# Top.net
KiCad netlist of a schematic drawn in Altium Designer
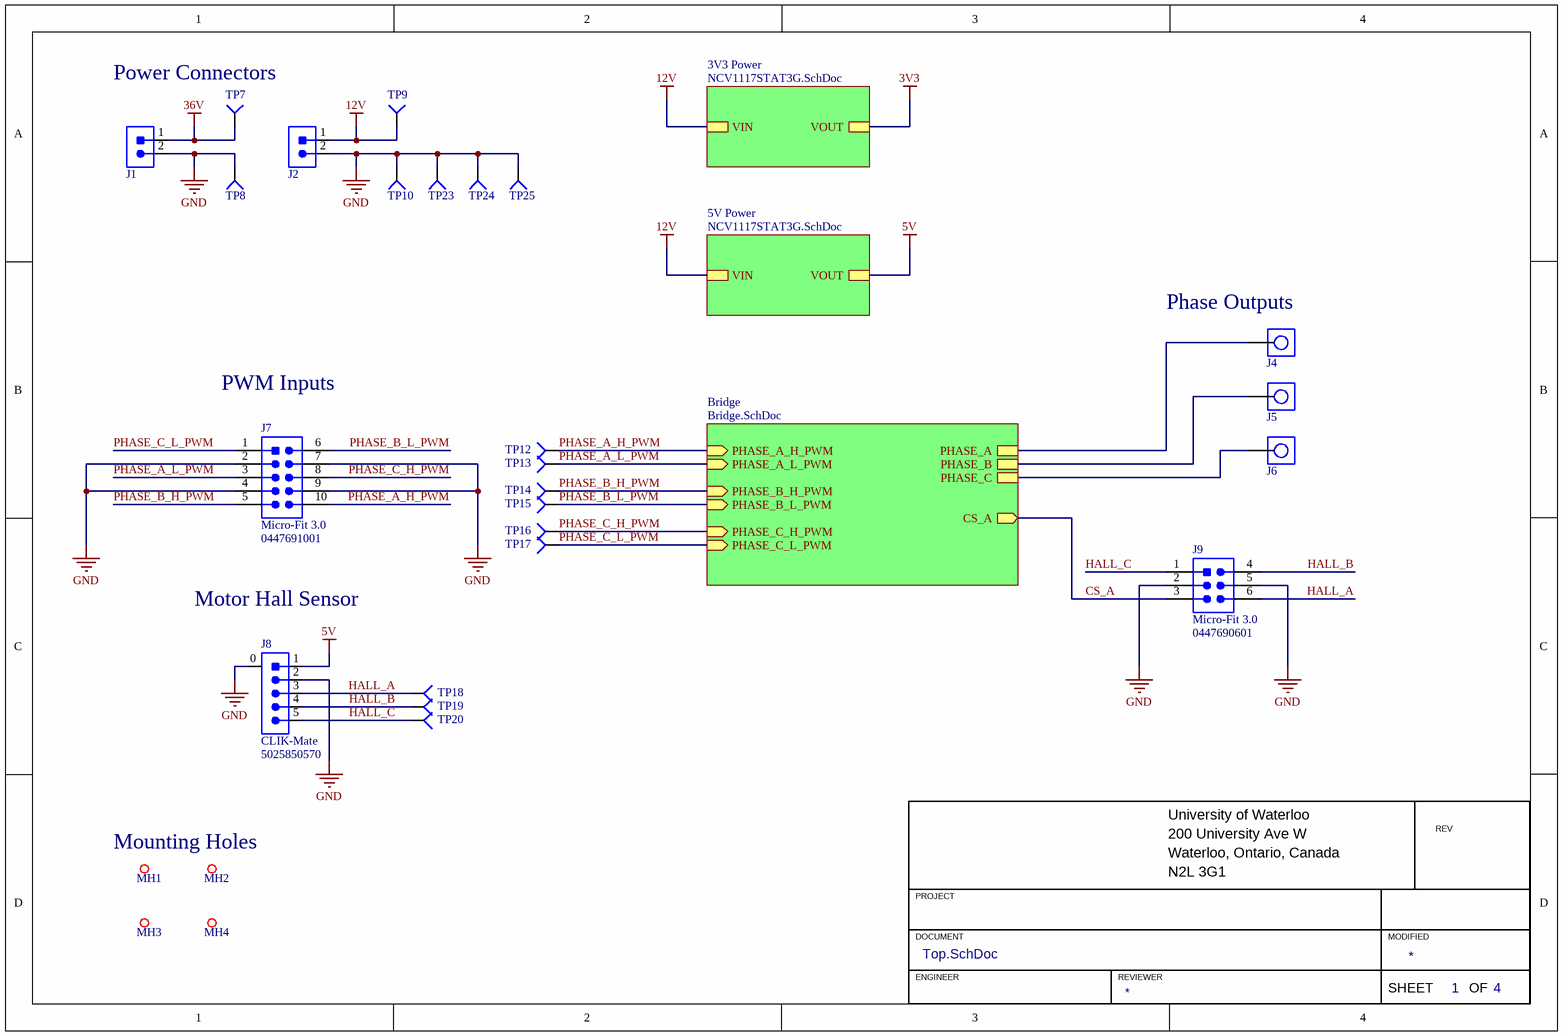
[diagram p0: Top.SchDoc]

(export (version "E")
  (design (tool "Eeschema 10.0.6"))
  (components
    (comp (ref "J1")
      (value "CON_2POS_XT90")
      (footprint "XT90")
      (description "XT60 CONNECTORS MALE/FEMALE PAIR")
      (libsource (lib "Personal_Schematic_Library_2022") (part "CON_2POS_XT90"))
    )
    (comp (ref "J2")
      (value "CON_2POS_XT60")
      (footprint "XT60")
      (description "XT60 CONNECTORS MALE/FEMALE PAIR")
      (libsource (lib "Personal_Schematic_Library_2022") (part "CON_2POS_XT60"))
    )
    (comp (ref "J4")
      (value "CT3151SP-4")
      (footprint "CALTEST_BANANA_JACK_YELLOW")
      (description "CONN BANANA JACK SOLDER YELLOW")
      (libsource (lib "UWRT_Schematic_Library_2020") (part "CON_BANANA_YELLOW_25A"))
    )
    (comp (ref "J5")
      (value "CT3151SP-5")
      (footprint "CALTEST_BANANA_JACK_GREEN")
      (description "CONN BANANA JACK SOLDER GREEN")
      (libsource (lib "UWRT_Schematic_Library_2020") (part "CON_BANANA_GREEN_25A"))
    )
    (comp (ref "J6")
      (value "CT3151SP-6")
      (footprint "CALTEST_BANANA_JACK_BLUE")
      (description "CONN BANANA JACK SOLDER BLUE")
      (libsource (lib "UWRT_Schematic_Library_2020") (part "CON_BANANA_BLUE_25A"))
    )
    (comp (ref "J7")
      (value "0447691001")
      (footprint "MOLEX-0447691001")
      (description "CONN RCPT 10POS 0.118 TIN PCB")
      (fields
        (field (name "FAMILY") "Micro-Fit 3.0")
        (field (name "MANUFACTURER PART NUMBER 1") "0447691001")
      )
      (libsource (lib "UWRT_Schematic_Library_2020") (part "CON_MOLEX-RCPT_5x2_TH"))
    )
    (comp (ref "J8")
      (value "CON_5M_SM_RA")
      (footprint "MOLEX-5025850570")
      (description "CONN HEADER SMD RIGHT ANGLE 1.5MM PITCH")
      (fields (field (name "FAMILY") "CLIK-Mate") (field (name "MANUFACTURER PART NUMBER 1") "5025850570"))
      (libsource (lib "UWRT_Schematic_Library_2020") (part "CON_5M_SM_RA"))
    )
    (comp (ref "J9")
      (value "0447690601")
      (footprint "MOLEX-0447690601")
      (description "CONN RCPT 6POS 0.118 TIN PCB")
      (fields
        (field (name "FAMILY") "Micro-Fit 3.0")
        (field (name "MANUFACTURER PART NUMBER 1") "0447690601")
      )
      (libsource (lib "UWRT_Schematic_Library_2020") (part "CON_MOLEX-RCPT_3x2_TH"))
    )
    (comp (ref "MH1")
      (value "MOUNTING_HOLE_M3")
      (footprint "MOUNTING_HOLE_3mm")
      (libsource (lib "UWRT_Schematic_Library_2020") (part "MOUNTING_HOLE_M3"))
    )
    (comp (ref "MH2")
      (value "MOUNTING_HOLE_M3")
      (footprint "MOUNTING_HOLE_3mm")
      (libsource (lib "UWRT_Schematic_Library_2020") (part "MOUNTING_HOLE_M3"))
    )
    (comp (ref "MH3")
      (value "MOUNTING_HOLE_M3")
      (footprint "MOUNTING_HOLE_3mm")
      (libsource (lib "UWRT_Schematic_Library_2020") (part "MOUNTING_HOLE_M3"))
    )
    (comp (ref "MH4")
      (value "MOUNTING_HOLE_M3")
      (footprint "MOUNTING_HOLE_3mm")
      (libsource (lib "UWRT_Schematic_Library_2020") (part "MOUNTING_HOLE_M3"))
    )
    (comp (ref "TP7")
      (value "TESTPOINT_SMD_LOOP")
      (footprint "S1751-46R")
      (description "TESTPOINT SMD LOOP")
      (libsource (lib "UWRT_Schematic_Library_2020") (part "TESTPOINT_SMD_LOOP"))
    )
    (comp (ref "TP8")
      (value "TESTPOINT_SMD_LOOP")
      (footprint "S1751-46R")
      (description "TESTPOINT SMD LOOP")
      (libsource (lib "UWRT_Schematic_Library_2020") (part "TESTPOINT_SMD_LOOP"))
    )
    (comp (ref "TP9")
      (value "TESTPOINT_SMD_LOOP")
      (footprint "S1751-46R")
      (description "TESTPOINT SMD LOOP")
      (libsource (lib "UWRT_Schematic_Library_2020") (part "TESTPOINT_SMD_LOOP"))
    )
    (comp (ref "TP10")
      (value "TESTPOINT_SMD_LOOP")
      (footprint "S1751-46R")
      (description "TESTPOINT SMD LOOP")
      (libsource (lib "UWRT_Schematic_Library_2020") (part "TESTPOINT_SMD_LOOP"))
    )
    (comp (ref "TP12")
      (value "TESTPOINT_1MM_CIRCLE")
      (footprint "TESTPOINT_CIRCLE_1MM")
      (description "TESTPOINT 1MM CIRCLE")
      (libsource (lib "UWRT_Schematic_Library_2020") (part "TESTPOINT_1MM_CIRCLE"))
    )
    (comp (ref "TP13")
      (value "TESTPOINT_1MM_CIRCLE")
      (footprint "TESTPOINT_CIRCLE_1MM")
      (description "TESTPOINT 1MM CIRCLE")
      (libsource (lib "UWRT_Schematic_Library_2020") (part "TESTPOINT_1MM_CIRCLE"))
    )
    (comp (ref "TP14")
      (value "TESTPOINT_1MM_CIRCLE")
      (footprint "TESTPOINT_CIRCLE_1MM")
      (description "TESTPOINT 1MM CIRCLE")
      (libsource (lib "UWRT_Schematic_Library_2020") (part "TESTPOINT_1MM_CIRCLE"))
    )
    (comp (ref "TP15")
      (value "TESTPOINT_1MM_CIRCLE")
      (footprint "TESTPOINT_CIRCLE_1MM")
      (description "TESTPOINT 1MM CIRCLE")
      (libsource (lib "UWRT_Schematic_Library_2020") (part "TESTPOINT_1MM_CIRCLE"))
    )
    (comp (ref "TP16")
      (value "TESTPOINT_1MM_CIRCLE")
      (footprint "TESTPOINT_CIRCLE_1MM")
      (description "TESTPOINT 1MM CIRCLE")
      (libsource (lib "UWRT_Schematic_Library_2020") (part "TESTPOINT_1MM_CIRCLE"))
    )
    (comp (ref "TP17")
      (value "TESTPOINT_1MM_CIRCLE")
      (footprint "TESTPOINT_CIRCLE_1MM")
      (description "TESTPOINT 1MM CIRCLE")
      (libsource (lib "UWRT_Schematic_Library_2020") (part "TESTPOINT_1MM_CIRCLE"))
    )
    (comp (ref "TP18")
      (value "TESTPOINT_1MM_CIRCLE")
      (footprint "TESTPOINT_CIRCLE_1MM")
      (description "TESTPOINT 1MM CIRCLE")
      (libsource (lib "UWRT_Schematic_Library_2020") (part "TESTPOINT_1MM_CIRCLE"))
    )
    (comp (ref "TP19")
      (value "TESTPOINT_1MM_CIRCLE")
      (footprint "TESTPOINT_CIRCLE_1MM")
      (description "TESTPOINT 1MM CIRCLE")
      (libsource (lib "UWRT_Schematic_Library_2020") (part "TESTPOINT_1MM_CIRCLE"))
    )
    (comp (ref "TP20")
      (value "TESTPOINT_1MM_CIRCLE")
      (footprint "TESTPOINT_CIRCLE_1MM")
      (description "TESTPOINT 1MM CIRCLE")
      (libsource (lib "UWRT_Schematic_Library_2020") (part "TESTPOINT_1MM_CIRCLE"))
    )
    (comp (ref "TP23")
      (value "TESTPOINT_SMD_LOOP")
      (footprint "S1751-46R")
      (description "TESTPOINT SMD LOOP")
      (libsource (lib "UWRT_Schematic_Library_2020") (part "TESTPOINT_SMD_LOOP"))
    )
    (comp (ref "TP24")
      (value "TESTPOINT_SMD_LOOP")
      (footprint "S1751-46R")
      (description "TESTPOINT SMD LOOP")
      (libsource (lib "UWRT_Schematic_Library_2020") (part "TESTPOINT_SMD_LOOP"))
    )
    (comp (ref "TP25")
      (value "TESTPOINT_SMD_LOOP")
      (footprint "S1751-46R")
      (description "TESTPOINT SMD LOOP")
      (libsource (lib "UWRT_Schematic_Library_2020") (part "TESTPOINT_SMD_LOOP"))
    )
  )
  (nets
    (net (code "1") (name "/CS_A") (class "Default")
      (node (ref "J9") (pin "3") (pinfunction "3_3") (pintype "passive"))
    )
    (net (code "2") (name "/HALL_A") (class "Default")
      (node (ref "J8") (pin "3") (pinfunction "3_3") (pintype "passive"))
      (node (ref "J9") (pin "6") (pinfunction "6_6") (pintype "passive"))
      (node (ref "TP18") (pin "1") (pinfunction "=value_1") (pintype "passive"))
    )
    (net (code "3") (name "/HALL_B") (class "Default")
      (node (ref "J8") (pin "4") (pinfunction "4_4") (pintype "passive"))
      (node (ref "J9") (pin "4") (pinfunction "4_4") (pintype "passive"))
      (node (ref "TP19") (pin "1") (pinfunction "=value_1") (pintype "passive"))
    )
    (net (code "4") (name "/HALL_C") (class "Default")
      (node (ref "J8") (pin "5") (pinfunction "5_5") (pintype "passive"))
      (node (ref "J9") (pin "1") (pinfunction "1_1") (pintype "passive"))
      (node (ref "TP20") (pin "1") (pinfunction "=value_1") (pintype "passive"))
    )
    (net (code "5") (name "/PHASE_A") (class "Default")
      (node (ref "J4") (pin "1") (pinfunction "1_1") (pintype "power_in"))
    )
    (net (code "6") (name "/PHASE_A_H_PWM") (class "Default")
      (node (ref "J7") (pin "10") (pinfunction "10_10") (pintype "passive"))
      (node (ref "TP12") (pin "1") (pinfunction "=value_1") (pintype "passive"))
    )
    (net (code "7") (name "/PHASE_A_L_PWM") (class "Default")
      (node (ref "J7") (pin "3") (pinfunction "3_3") (pintype "passive"))
      (node (ref "TP13") (pin "1") (pinfunction "=value_1") (pintype "passive"))
    )
    (net (code "8") (name "/PHASE_B") (class "Default")
      (node (ref "J5") (pin "1") (pinfunction "1_1") (pintype "power_in"))
    )
    (net (code "9") (name "/PHASE_B_H_PWM") (class "Default")
      (node (ref "J7") (pin "5") (pinfunction "5_5") (pintype "passive"))
      (node (ref "TP14") (pin "1") (pinfunction "=value_1") (pintype "passive"))
    )
    (net (code "10") (name "/PHASE_B_L_PWM") (class "Default")
      (node (ref "J7") (pin "6") (pinfunction "6_6") (pintype "passive"))
      (node (ref "TP15") (pin "1") (pinfunction "=value_1") (pintype "passive"))
    )
    (net (code "11") (name "/PHASE_C") (class "Default")
      (node (ref "J6") (pin "1") (pinfunction "1_1") (pintype "power_in"))
    )
    (net (code "12") (name "/PHASE_C_H_PWM") (class "Default")
      (node (ref "J7") (pin "8") (pinfunction "8_8") (pintype "passive"))
      (node (ref "TP16") (pin "1") (pinfunction "=value_1") (pintype "passive"))
    )
    (net (code "13") (name "/PHASE_C_L_PWM") (class "Default")
      (node (ref "J7") (pin "1") (pinfunction "1_1") (pintype "passive"))
      (node (ref "TP17") (pin "1") (pinfunction "=value_1") (pintype "passive"))
    )
    (net (code "15") (name "5V") (class "Default")
      (node (ref "J8") (pin "1") (pinfunction "1_1") (pintype "passive"))
    )
    (net (code "16") (name "12V") (class "Default")
      (node (ref "J2") (pin "1") (pinfunction "1_1") (pintype "passive"))
      (node (ref "TP9") (pin "1") (pinfunction "=value_1") (pintype "passive"))
    )
    (net (code "17") (name "36V") (class "Default")
      (node (ref "J1") (pin "1") (pinfunction "1_1") (pintype "passive"))
      (node (ref "TP7") (pin "1") (pinfunction "=value_1") (pintype "passive"))
    )
    (net (code "18") (name "GND") (class "Default")
      (node (ref "J1") (pin "2") (pinfunction "2_2") (pintype "passive"))
      (node (ref "J2") (pin "2") (pinfunction "2_2") (pintype "passive"))
      (node (ref "J7") (pin "2") (pinfunction "2_2") (pintype "passive"))
      (node (ref "J7") (pin "4") (pinfunction "4_4") (pintype "passive"))
      (node (ref "J7") (pin "7") (pinfunction "7_7") (pintype "passive"))
      (node (ref "J7") (pin "9") (pinfunction "9_9") (pintype "passive"))
      (node (ref "J8") (pin "0") (pinfunction "0_0") (pintype "passive"))
      (node (ref "J8") (pin "2") (pinfunction "2_2") (pintype "passive"))
      (node (ref "J9") (pin "2") (pinfunction "2_2") (pintype "passive"))
      (node (ref "J9") (pin "5") (pinfunction "5_5") (pintype "passive"))
      (node (ref "TP10") (pin "1") (pinfunction "=value_1") (pintype "passive"))
      (node (ref "TP23") (pin "1") (pinfunction "=value_1") (pintype "passive"))
      (node (ref "TP24") (pin "1") (pinfunction "=value_1") (pintype "passive"))
      (node (ref "TP25") (pin "1") (pinfunction "=value_1") (pintype "passive"))
      (node (ref "TP8") (pin "1") (pinfunction "=value_1") (pintype "passive"))
    )
  )
)
